# Filamint_Schematic_V4_4.net
KiCad netlist of a schematic drawn in EAGLE
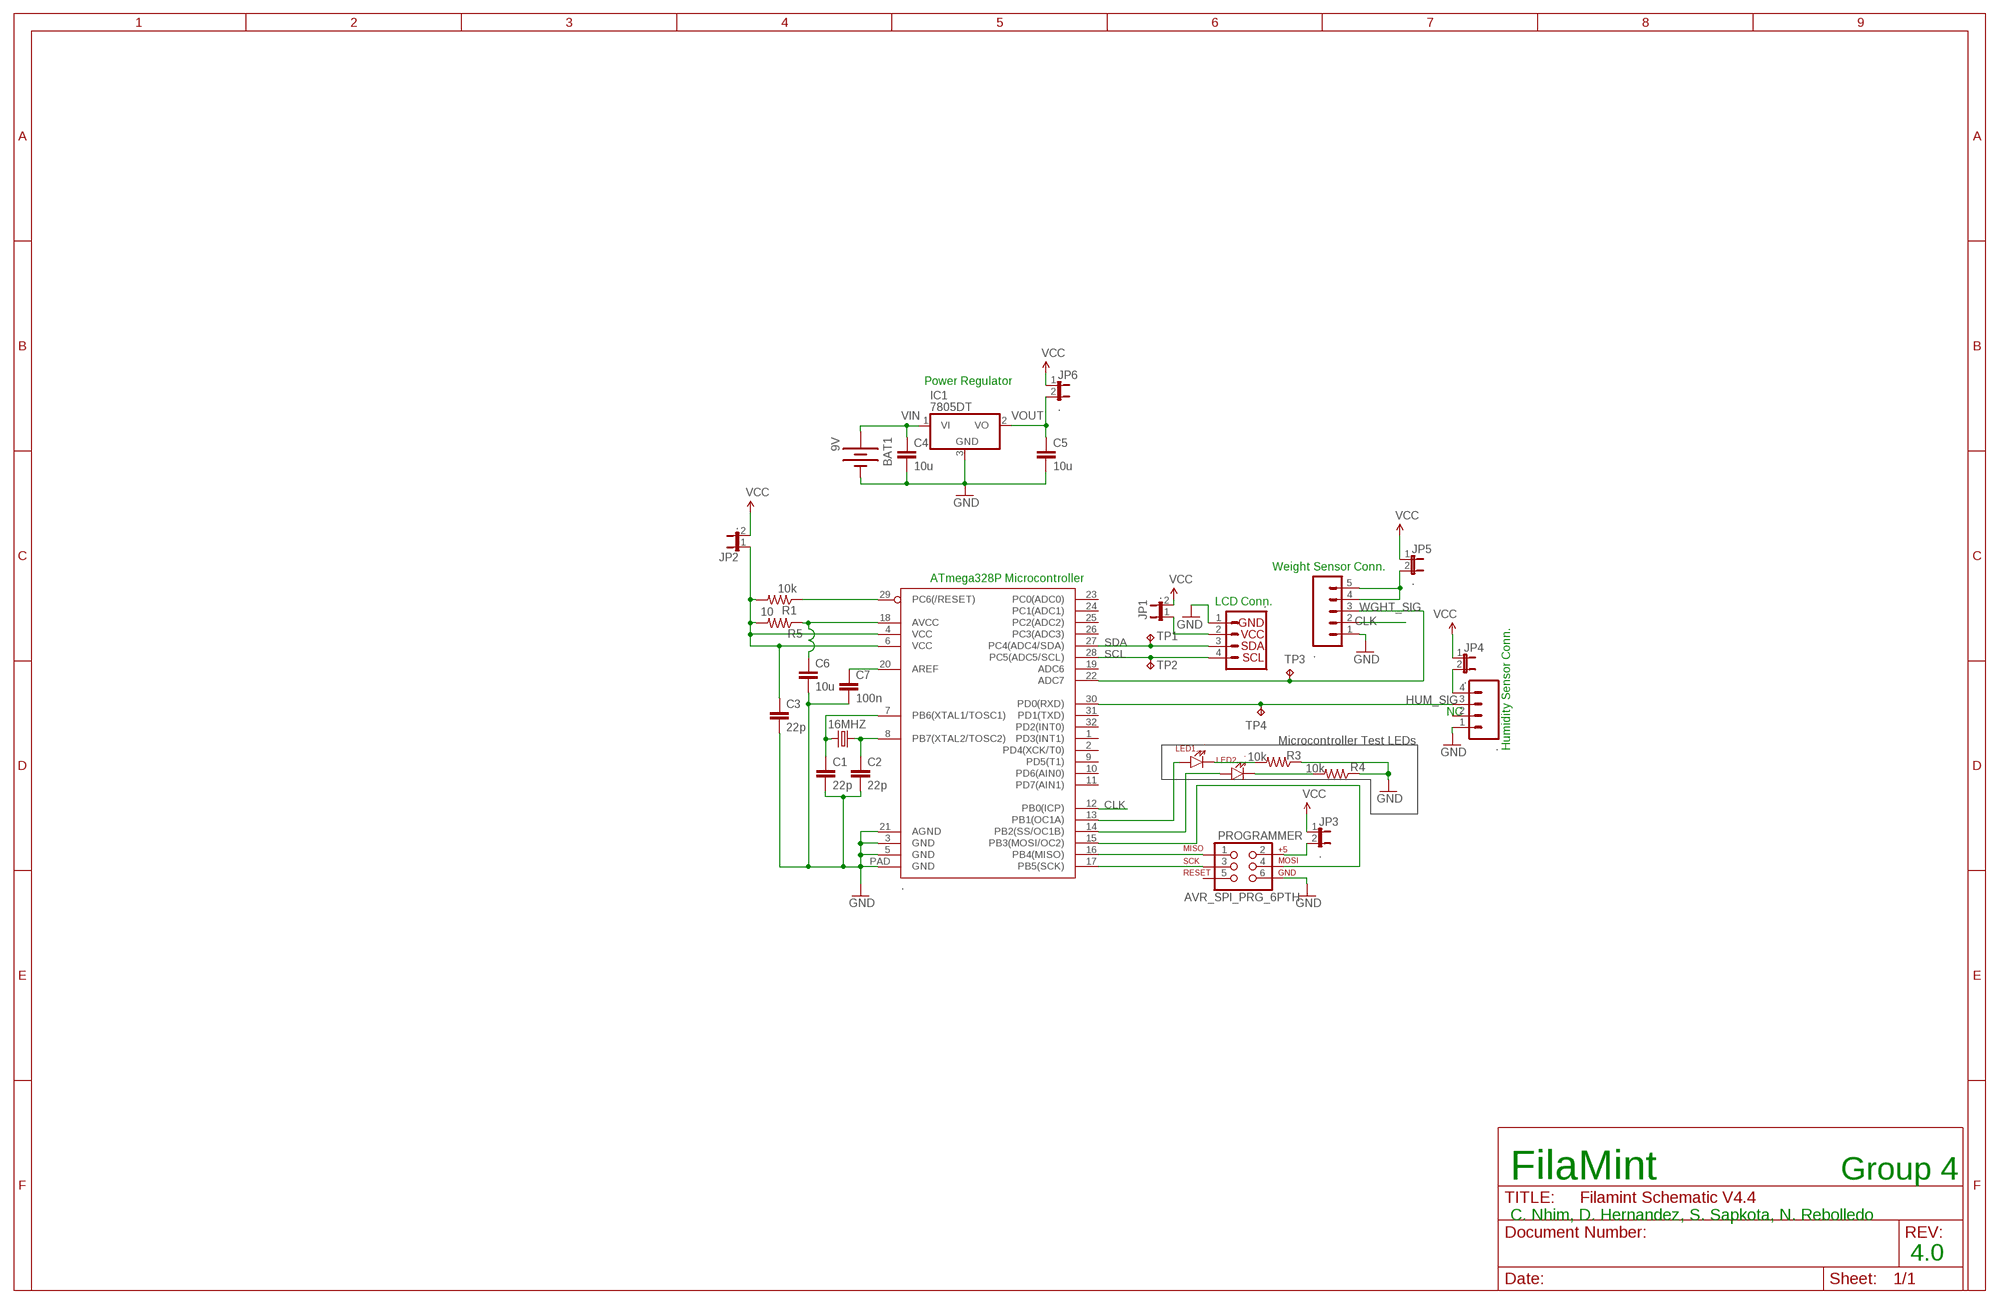
[diagram p0: schematic, sheet 1]

(export (version "E")
  (design (tool "Eeschema 10.0.6"))
  (components
    (comp (ref "16MHZ")
      (value "CSM-7X-DU")
      (footprint "eagle-import:CSM-7X-DU")
      (libsource (lib "eagle-import") (part "CSM-7X-DU"))
    )
    (comp (ref "BAT1")
      (value "9V")
      (footprint "eagle-import:BATTCON_9V")
      (libsource (lib "eagle-import") (part "BATTERY9V"))
    )
    (comp (ref "C1")
      (value "22p")
      (footprint "eagle-import:C025-024X044")
      (libsource (lib "eagle-import") (part "C-EU025-024X044"))
    )
    (comp (ref "C2")
      (value "22p")
      (footprint "eagle-import:C025-024X044")
      (libsource (lib "eagle-import") (part "C-EU025-024X044"))
    )
    (comp (ref "C3")
      (value "22p")
      (footprint "eagle-import:C025-024X044")
      (libsource (lib "eagle-import") (part "C-EU025-024X044"))
    )
    (comp (ref "C4")
      (value "10u")
      (footprint "eagle-import:C025-024X044")
      (libsource (lib "eagle-import") (part "C-EU025-024X044"))
    )
    (comp (ref "C5")
      (value "10u")
      (footprint "eagle-import:C025-024X044")
      (libsource (lib "eagle-import") (part "C-EU025-024X044"))
    )
    (comp (ref "C6")
      (value "10u")
      (footprint "eagle-import:C025-024X044")
      (libsource (lib "eagle-import") (part "C-EU025-024X044"))
    )
    (comp (ref "C7")
      (value "100n")
      (footprint "eagle-import:C025-024X044")
      (libsource (lib "eagle-import") (part "C-EU025-024X044"))
    )
    (comp (ref "DHT22")
      (value ".")
      (footprint "eagle-import:1X04-1MM-RA")
      (libsource (lib "eagle-import") (part "M04SMD2"))
    )
    (comp (ref "HX711")
      (value ".")
      (footprint "eagle-import:1X05-1MM")
      (libsource (lib "eagle-import") (part "M05SMD"))
    )
    (comp (ref "IC1")
      (value "7805DT")
      (footprint "eagle-import:TO252")
      (libsource (lib "eagle-import") (part "78DT05"))
    )
    (comp (ref "JP1")
      (value ".")
      (footprint "eagle-import:JP1")
      (libsource (lib "eagle-import") (part "JP1E"))
    )
    (comp (ref "JP2")
      (value ".")
      (footprint "eagle-import:JP1")
      (libsource (lib "eagle-import") (part "JP1E"))
    )
    (comp (ref "JP3")
      (value ".")
      (footprint "eagle-import:JP1")
      (libsource (lib "eagle-import") (part "JP1E"))
    )
    (comp (ref "JP4")
      (value ".")
      (footprint "eagle-import:JP1")
      (libsource (lib "eagle-import") (part "JP1E"))
    )
    (comp (ref "JP5")
      (value ".")
      (footprint "eagle-import:JP1")
      (libsource (lib "eagle-import") (part "JP1E"))
    )
    (comp (ref "JP6")
      (value ".")
      (footprint "eagle-import:JP1")
      (libsource (lib "eagle-import") (part "JP1E"))
    )
    (comp (ref "LCD")
      (value ".")
      (footprint "eagle-import:1X04")
      (libsource (lib "eagle-import") (part "I2C_STANDARD"))
    )
    (comp (ref "LED1")
      (value ".")
      (footprint "eagle-import:LTE-302")
      (libsource (lib "eagle-import") (part "LTE-302"))
    )
    (comp (ref "LED2")
      (value ".")
      (footprint "eagle-import:LTE-302")
      (libsource (lib "eagle-import") (part "LTE-302"))
    )
    (comp (ref "MICROCONTROLLER")
      (value ".")
      (footprint "eagle-import:MLF32-PAD")
      (libsource (lib "eagle-import") (part "ATMEGA328P_MLFMLF32"))
    )
    (comp (ref "PROGRAMMER")
      (value "AVR_SPI_PRG_6PTH")
      (footprint "eagle-import:2X3")
      (libsource (lib "eagle-import") (part "AVR_SPI_PRG_6PTH"))
    )
    (comp (ref "R1")
      (value "10k")
      (footprint "eagle-import:0204_5")
      (libsource (lib "eagle-import") (part "R-US_0204/5"))
    )
    (comp (ref "R3")
      (value "10k")
      (footprint "eagle-import:0204_5")
      (libsource (lib "eagle-import") (part "R-US_0204/5"))
    )
    (comp (ref "R4")
      (value "10k")
      (footprint "eagle-import:0204_5")
      (libsource (lib "eagle-import") (part "R-US_0204/5"))
    )
    (comp (ref "R5")
      (value "10")
      (footprint "eagle-import:0204_5")
      (libsource (lib "eagle-import") (part "R-US_0204/5"))
    )
    (comp (ref "TP1")
      (value "TPB1,27")
      (footprint "eagle-import:B1,27")
      (libsource (lib "eagle-import") (part "TPB1,27"))
    )
    (comp (ref "TP2")
      (value "TPB1,27")
      (footprint "eagle-import:B1,27")
      (libsource (lib "eagle-import") (part "TPB1,27"))
    )
    (comp (ref "TP3")
      (value "TPB1,27")
      (footprint "eagle-import:B1,27")
      (libsource (lib "eagle-import") (part "TPB1,27"))
    )
    (comp (ref "TP4")
      (value "TPB1,27")
      (footprint "eagle-import:B1,27")
      (libsource (lib "eagle-import") (part "TPB1,27"))
    )
  )
  (nets
    (net (code "1") (name "/CLK") (class "Default")
      (node (ref "HX711") (pin "2") (pinfunction "2_2") (pintype "passive"))
      (node (ref "MICROCONTROLLER") (pin "12") (pinfunction "PB0(ICP)_12") (pintype "bidirectional"))
    )
    (net (code "2") (name "/HUM_SIG") (class "Default")
      (node (ref "DHT22") (pin "3") (pinfunction "3_3") (pintype "passive"))
      (node (ref "MICROCONTROLLER") (pin "30") (pinfunction "PD0(RXD)_30") (pintype "bidirectional"))
      (node (ref "TP4") (pin "TP") (pinfunction "TP_TP") (pintype "input"))
    )
    (net (code "3") (name "/SCL") (class "Default")
      (node (ref "LCD") (pin "4") (pinfunction "4_4") (pintype "passive"))
      (node (ref "MICROCONTROLLER") (pin "28") (pinfunction "PC5(ADC5/SCL)_28") (pintype "bidirectional"))
      (node (ref "TP2") (pin "TP") (pinfunction "TP_TP") (pintype "input"))
    )
    (net (code "4") (name "/SDA") (class "Default")
      (node (ref "LCD") (pin "3") (pinfunction "3_3") (pintype "passive"))
      (node (ref "MICROCONTROLLER") (pin "27") (pinfunction "PC4(ADC4/SDA)_27") (pintype "bidirectional"))
      (node (ref "TP1") (pin "TP") (pinfunction "TP_TP") (pintype "input"))
    )
    (net (code "5") (name "/VIN") (class "Default")
      (node (ref "BAT1") (pin "+") (pinfunction "+_+") (pintype "power_in"))
      (node (ref "C4") (pin "1") (pinfunction "1_1") (pintype "passive"))
      (node (ref "IC1") (pin "1") (pinfunction "VI_1") (pintype "input"))
    )
    (net (code "6") (name "/WGHT_SIG") (class "Default")
      (node (ref "HX711") (pin "3") (pinfunction "3_3") (pintype "passive"))
      (node (ref "MICROCONTROLLER") (pin "22") (pinfunction "ADC7_22") (pintype "bidirectional"))
      (node (ref "TP3") (pin "TP") (pinfunction "TP_TP") (pintype "input"))
    )
    (net (code "7") (name "GND") (class "Default")
      (node (ref "BAT1") (pin "-") (pinfunction "-_-") (pintype "power_in"))
      (node (ref "C1") (pin "2") (pinfunction "2_2") (pintype "passive"))
      (node (ref "C2") (pin "2") (pinfunction "2_2") (pintype "passive"))
      (node (ref "C3") (pin "2") (pinfunction "2_2") (pintype "passive"))
      (node (ref "C4") (pin "2") (pinfunction "2_2") (pintype "passive"))
      (node (ref "C5") (pin "2") (pinfunction "2_2") (pintype "passive"))
      (node (ref "C6") (pin "2") (pinfunction "2_2") (pintype "passive"))
      (node (ref "C7") (pin "2") (pinfunction "2_2") (pintype "passive"))
      (node (ref "DHT22") (pin "1") (pinfunction "1_1") (pintype "passive"))
      (node (ref "HX711") (pin "1") (pinfunction "1_1") (pintype "passive"))
      (node (ref "IC1") (pin "3") (pinfunction "GND_3") (pintype "passive"))
      (node (ref "LCD") (pin "1") (pinfunction "1_1") (pintype "passive"))
      (node (ref "MICROCONTROLLER") (pin "21") (pinfunction "AGND_21") (pintype "bidirectional"))
      (node (ref "MICROCONTROLLER") (pin "3") (pinfunction "GND_3") (pintype "bidirectional"))
      (node (ref "MICROCONTROLLER") (pin "5") (pinfunction "GND_5") (pintype "bidirectional"))
      (node (ref "MICROCONTROLLER") (pin "PAD") (pinfunction "GND_PAD") (pintype "bidirectional"))
      (node (ref "PROGRAMMER") (pin "6") (pinfunction "6_6") (pintype "passive"))
      (node (ref "R3") (pin "1") (pinfunction "1_1") (pintype "passive"))
      (node (ref "R4") (pin "1") (pinfunction "1_1") (pintype "passive"))
    )
    (net (code "8") (name "Net-(C3-Pad1)") (class "Default")
      (node (ref "C3") (pin "1") (pinfunction "1_1") (pintype "passive"))
      (node (ref "JP2") (pin "1") (pinfunction "1_1") (pintype "passive"))
      (node (ref "MICROCONTROLLER") (pin "4") (pinfunction "VCC_4") (pintype "bidirectional"))
      (node (ref "MICROCONTROLLER") (pin "6") (pinfunction "VCC_6") (pintype "bidirectional"))
      (node (ref "R1") (pin "2") (pinfunction "2_2") (pintype "passive"))
      (node (ref "R5") (pin "2") (pinfunction "2_2") (pintype "passive"))
    )
    (net (code "9") (name "Net-(DHT22-Pad4)") (class "Default")
      (node (ref "DHT22") (pin "4") (pinfunction "4_4") (pintype "passive"))
      (node (ref "JP4") (pin "2") (pinfunction "2_2") (pintype "passive"))
    )
    (net (code "10") (name "Net-(HX711-Pad4)") (class "Default")
      (node (ref "HX711") (pin "4") (pinfunction "4_4") (pintype "passive"))
      (node (ref "HX711") (pin "5") (pinfunction "5_5") (pintype "passive"))
      (node (ref "JP5") (pin "2") (pinfunction "2_2") (pintype "passive"))
    )
    (net (code "11") (name "Net-(IC1-VO)") (class "Default")
      (node (ref "C5") (pin "1") (pinfunction "1_1") (pintype "passive"))
      (node (ref "IC1") (pin "2") (pinfunction "VO_2") (pintype "passive"))
      (node (ref "JP6") (pin "2") (pinfunction "2_2") (pintype "passive"))
    )
    (net (code "12") (name "Net-(JP1-Pad1)") (class "Default")
      (node (ref "JP1") (pin "1") (pinfunction "1_1") (pintype "passive"))
      (node (ref "LCD") (pin "2") (pinfunction "2_2") (pintype "passive"))
    )
    (net (code "13") (name "Net-(JP3-Pad2)") (class "Default")
      (node (ref "JP3") (pin "2") (pinfunction "2_2") (pintype "passive"))
      (node (ref "PROGRAMMER") (pin "2") (pinfunction "2_2") (pintype "passive"))
    )
    (net (code "14") (name "Net-(LED1-PadC)") (class "Default")
      (node (ref "LED1") (pin "C") (pinfunction "C_C") (pintype "bidirectional"))
      (node (ref "R3") (pin "2") (pinfunction "2_2") (pintype "passive"))
    )
    (net (code "15") (name "Net-(LED2-PadC)") (class "Default")
      (node (ref "LED2") (pin "C") (pinfunction "C_C") (pintype "bidirectional"))
      (node (ref "R4") (pin "2") (pinfunction "2_2") (pintype "passive"))
    )
    (net (code "16") (name "Net-(MICROCONTROLLER-AREF)") (class "Default")
      (node (ref "C7") (pin "1") (pinfunction "1_1") (pintype "passive"))
      (node (ref "MICROCONTROLLER") (pin "20") (pinfunction "AREF_20") (pintype "bidirectional"))
    )
    (net (code "17") (name "Net-(MICROCONTROLLER-AVCC)") (class "Default")
      (node (ref "C6") (pin "1") (pinfunction "1_1") (pintype "passive"))
      (node (ref "MICROCONTROLLER") (pin "18") (pinfunction "AVCC_18") (pintype "bidirectional"))
      (node (ref "R5") (pin "1") (pinfunction "1_1") (pintype "passive"))
    )
    (net (code "18") (name "Net-(MICROCONTROLLER-PB1(OC1A))") (class "Default")
      (node (ref "LED1") (pin "A") (pinfunction "A_A") (pintype "bidirectional"))
      (node (ref "MICROCONTROLLER") (pin "13") (pinfunction "PB1(OC1A)_13") (pintype "bidirectional"))
    )
    (net (code "19") (name "Net-(MICROCONTROLLER-PB2(SS{slash}OC1B))") (class "Default")
      (node (ref "LED2") (pin "A") (pinfunction "A_A") (pintype "bidirectional"))
      (node (ref "MICROCONTROLLER") (pin "14") (pinfunction "PB2(SS/OC1B)_14") (pintype "bidirectional"))
    )
    (net (code "20") (name "Net-(MICROCONTROLLER-PB3(MOSI{slash}OC2))") (class "Default")
      (node (ref "MICROCONTROLLER") (pin "15") (pinfunction "PB3(MOSI/OC2)_15") (pintype "bidirectional"))
      (node (ref "PROGRAMMER") (pin "4") (pinfunction "4_4") (pintype "passive"))
    )
    (net (code "21") (name "Net-(MICROCONTROLLER-PB4(MISO))") (class "Default")
      (node (ref "MICROCONTROLLER") (pin "16") (pinfunction "PB4(MISO)_16") (pintype "bidirectional"))
      (node (ref "PROGRAMMER") (pin "1") (pinfunction "1_1") (pintype "passive"))
    )
    (net (code "22") (name "Net-(MICROCONTROLLER-PB5(SCK))") (class "Default")
      (node (ref "MICROCONTROLLER") (pin "17") (pinfunction "PB5(SCK)_17") (pintype "bidirectional"))
      (node (ref "PROGRAMMER") (pin "3") (pinfunction "3_3") (pintype "passive"))
    )
    (net (code "23") (name "Net-(MICROCONTROLLER-PB6(XTAL1{slash}TOSC1))") (class "Default")
      (node (ref "16MHZ") (pin "2") (pinfunction "2_2") (pintype "passive"))
      (node (ref "C1") (pin "1") (pinfunction "1_1") (pintype "passive"))
      (node (ref "MICROCONTROLLER") (pin "7") (pinfunction "PB6(XTAL1/TOSC1)_7") (pintype "bidirectional"))
    )
    (net (code "24") (name "Net-(MICROCONTROLLER-PB7(XTAL2{slash}TOSC2))") (class "Default")
      (node (ref "16MHZ") (pin "1") (pinfunction "1_1") (pintype "passive"))
      (node (ref "C2") (pin "1") (pinfunction "1_1") (pintype "passive"))
      (node (ref "MICROCONTROLLER") (pin "8") (pinfunction "PB7(XTAL2/TOSC2)_8") (pintype "bidirectional"))
    )
    (net (code "25") (name "Net-(MICROCONTROLLER-PC6({slash}RESET))") (class "Default")
      (node (ref "MICROCONTROLLER") (pin "29") (pinfunction "PC6(/RESET)_29") (pintype "bidirectional"))
      (node (ref "R1") (pin "1") (pinfunction "1_1") (pintype "passive"))
    )
    (net (code "26") (name "VCC") (class "Default")
      (node (ref "JP1") (pin "2") (pinfunction "2_2") (pintype "passive"))
      (node (ref "JP2") (pin "2") (pinfunction "2_2") (pintype "passive"))
      (node (ref "JP3") (pin "1") (pinfunction "1_1") (pintype "passive"))
      (node (ref "JP4") (pin "1") (pinfunction "1_1") (pintype "passive"))
      (node (ref "JP5") (pin "1") (pinfunction "1_1") (pintype "passive"))
      (node (ref "JP6") (pin "1") (pinfunction "1_1") (pintype "passive"))
    )
    (net (code "27") (name "unconnected-(DHT22-Pad2)") (class "Default")
      (node (ref "DHT22") (pin "2") (pinfunction "2_2") (pintype "passive"))
    )
    (net (code "28") (name "unconnected-(MICROCONTROLLER-ADC6-Pad19)") (class "Default")
      (node (ref "MICROCONTROLLER") (pin "19") (pinfunction "ADC6_19") (pintype "bidirectional"))
    )
    (net (code "29") (name "unconnected-(MICROCONTROLLER-PC0(ADC0)-Pad23)") (class "Default")
      (node (ref "MICROCONTROLLER") (pin "23") (pinfunction "PC0(ADC0)_23") (pintype "bidirectional"))
    )
    (net (code "30") (name "unconnected-(MICROCONTROLLER-PC1(ADC1)-Pad24)") (class "Default")
      (node (ref "MICROCONTROLLER") (pin "24") (pinfunction "PC1(ADC1)_24") (pintype "bidirectional"))
    )
    (net (code "31") (name "unconnected-(MICROCONTROLLER-PC2(ADC2)-Pad25)") (class "Default")
      (node (ref "MICROCONTROLLER") (pin "25") (pinfunction "PC2(ADC2)_25") (pintype "bidirectional"))
    )
    (net (code "32") (name "unconnected-(MICROCONTROLLER-PC3(ADC3)-Pad26)") (class "Default")
      (node (ref "MICROCONTROLLER") (pin "26") (pinfunction "PC3(ADC3)_26") (pintype "bidirectional"))
    )
    (net (code "33") (name "unconnected-(MICROCONTROLLER-PD1(TXD)-Pad31)") (class "Default")
      (node (ref "MICROCONTROLLER") (pin "31") (pinfunction "PD1(TXD)_31") (pintype "bidirectional"))
    )
    (net (code "34") (name "unconnected-(MICROCONTROLLER-PD2(INT0)-Pad32)") (class "Default")
      (node (ref "MICROCONTROLLER") (pin "32") (pinfunction "PD2(INT0)_32") (pintype "bidirectional"))
    )
    (net (code "35") (name "unconnected-(MICROCONTROLLER-PD3(INT1)-Pad1)") (class "Default")
      (node (ref "MICROCONTROLLER") (pin "1") (pinfunction "PD3(INT1)_1") (pintype "bidirectional"))
    )
    (net (code "36") (name "unconnected-(MICROCONTROLLER-PD4(XCK{slash}T0)-Pad2)") (class "Default")
      (node (ref "MICROCONTROLLER") (pin "2") (pinfunction "PD4(XCK/T0)_2") (pintype "bidirectional"))
    )
    (net (code "37") (name "unconnected-(MICROCONTROLLER-PD5(T1)-Pad9)") (class "Default")
      (node (ref "MICROCONTROLLER") (pin "9") (pinfunction "PD5(T1)_9") (pintype "bidirectional"))
    )
    (net (code "38") (name "unconnected-(MICROCONTROLLER-PD6(AIN0)-Pad10)") (class "Default")
      (node (ref "MICROCONTROLLER") (pin "10") (pinfunction "PD6(AIN0)_10") (pintype "bidirectional"))
    )
    (net (code "39") (name "unconnected-(MICROCONTROLLER-PD7(AIN1)-Pad11)") (class "Default")
      (node (ref "MICROCONTROLLER") (pin "11") (pinfunction "PD7(AIN1)_11") (pintype "bidirectional"))
    )
    (net (code "40") (name "unconnected-(PROGRAMMER-Pad5)") (class "Default")
      (node (ref "PROGRAMMER") (pin "5") (pinfunction "5_5") (pintype "passive"))
    )
  )
)
